# B163D.net
KiCad netlist of a schematic drawn in EAGLE
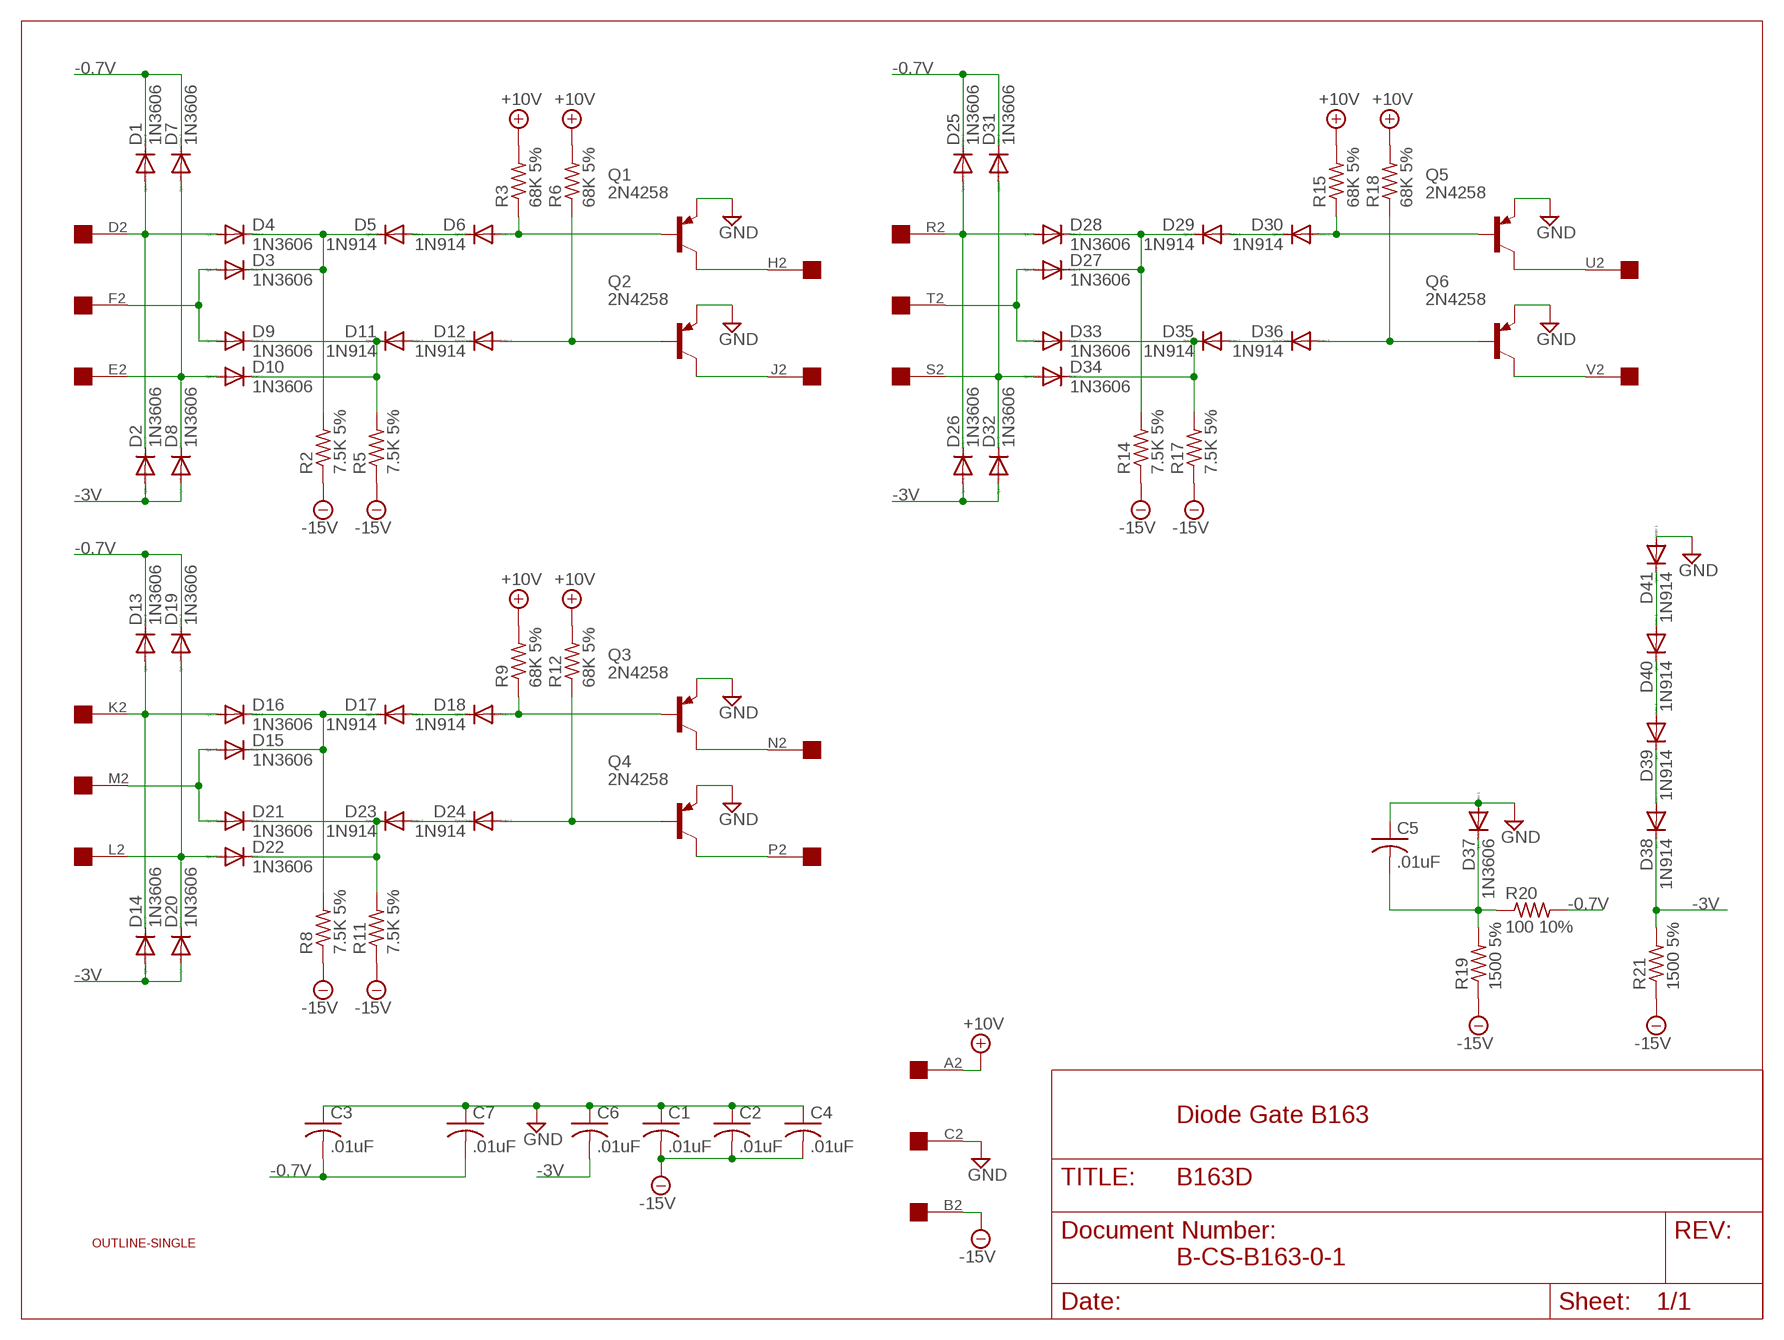
[diagram p0: schematic, sheet 1]

(export (version "E")
  (design (tool "Eeschema 10.0.6"))
  (components
    (comp (ref "C1")
      (value ".01uF")
      (footprint "eagle-import:C050-025X075")
      (libsource (lib "eagle-import") (part "C-US050-025X075"))
    )
    (comp (ref "C2")
      (value ".01uF")
      (footprint "eagle-import:C050-025X075")
      (libsource (lib "eagle-import") (part "C-US050-025X075"))
    )
    (comp (ref "C3")
      (value ".01uF")
      (footprint "eagle-import:C050-025X075")
      (libsource (lib "eagle-import") (part "C-US050-025X075"))
    )
    (comp (ref "C4")
      (value ".01uF")
      (footprint "eagle-import:C050-025X075")
      (libsource (lib "eagle-import") (part "C-US050-025X075"))
    )
    (comp (ref "C5")
      (value ".01uF")
      (footprint "eagle-import:C050-025X075")
      (libsource (lib "eagle-import") (part "C-US050-025X075"))
    )
    (comp (ref "C6")
      (value ".01uF")
      (footprint "eagle-import:C050-025X075")
      (libsource (lib "eagle-import") (part "C-US050-025X075"))
    )
    (comp (ref "C7")
      (value ".01uF")
      (footprint "eagle-import:C050-025X075")
      (libsource (lib "eagle-import") (part "C-US050-025X075"))
    )
    (comp (ref "D1")
      (value "1N3606")
      (footprint "eagle-import:DO35-10")
      (libsource (lib "eagle-import") (part "1N4148DO35-10"))
    )
    (comp (ref "D2")
      (value "1N3606")
      (footprint "eagle-import:DO35-10")
      (libsource (lib "eagle-import") (part "1N4148DO35-10"))
    )
    (comp (ref "D3")
      (value "1N3606")
      (footprint "eagle-import:DO35-10")
      (libsource (lib "eagle-import") (part "1N4148DO35-10"))
    )
    (comp (ref "D4")
      (value "1N3606")
      (footprint "eagle-import:DO35-10")
      (libsource (lib "eagle-import") (part "1N4148DO35-10"))
    )
    (comp (ref "D5")
      (value "1N914")
      (footprint "eagle-import:DO35-10")
      (libsource (lib "eagle-import") (part "1N4148DO35-10"))
    )
    (comp (ref "D6")
      (value "1N914")
      (footprint "eagle-import:DO35-10")
      (libsource (lib "eagle-import") (part "1N4148DO35-10"))
    )
    (comp (ref "D7")
      (value "1N3606")
      (footprint "eagle-import:DO35-10")
      (libsource (lib "eagle-import") (part "1N4148DO35-10"))
    )
    (comp (ref "D8")
      (value "1N3606")
      (footprint "eagle-import:DO35-10")
      (libsource (lib "eagle-import") (part "1N4148DO35-10"))
    )
    (comp (ref "D9")
      (value "1N3606")
      (footprint "eagle-import:DO35-10")
      (libsource (lib "eagle-import") (part "1N4148DO35-10"))
    )
    (comp (ref "D10")
      (value "1N3606")
      (footprint "eagle-import:DO35-10")
      (libsource (lib "eagle-import") (part "1N4148DO35-10"))
    )
    (comp (ref "D11")
      (value "1N914")
      (footprint "eagle-import:DO35-10")
      (libsource (lib "eagle-import") (part "1N4148DO35-10"))
    )
    (comp (ref "D12")
      (value "1N914")
      (footprint "eagle-import:DO35-10")
      (libsource (lib "eagle-import") (part "1N4148DO35-10"))
    )
    (comp (ref "D13")
      (value "1N3606")
      (footprint "eagle-import:DO35-10")
      (libsource (lib "eagle-import") (part "1N4148DO35-10"))
    )
    (comp (ref "D14")
      (value "1N3606")
      (footprint "eagle-import:DO35-10")
      (libsource (lib "eagle-import") (part "1N4148DO35-10"))
    )
    (comp (ref "D15")
      (value "1N3606")
      (footprint "eagle-import:DO35-10")
      (libsource (lib "eagle-import") (part "1N4148DO35-10"))
    )
    (comp (ref "D16")
      (value "1N3606")
      (footprint "eagle-import:DO35-10")
      (libsource (lib "eagle-import") (part "1N4148DO35-10"))
    )
    (comp (ref "D17")
      (value "1N914")
      (footprint "eagle-import:DO35-10")
      (libsource (lib "eagle-import") (part "1N4148DO35-10"))
    )
    (comp (ref "D18")
      (value "1N914")
      (footprint "eagle-import:DO35-10")
      (libsource (lib "eagle-import") (part "1N4148DO35-10"))
    )
    (comp (ref "D19")
      (value "1N3606")
      (footprint "eagle-import:DO35-10")
      (libsource (lib "eagle-import") (part "1N4148DO35-10"))
    )
    (comp (ref "D20")
      (value "1N3606")
      (footprint "eagle-import:DO35-10")
      (libsource (lib "eagle-import") (part "1N4148DO35-10"))
    )
    (comp (ref "D21")
      (value "1N3606")
      (footprint "eagle-import:DO35-10")
      (libsource (lib "eagle-import") (part "1N4148DO35-10"))
    )
    (comp (ref "D22")
      (value "1N3606")
      (footprint "eagle-import:DO35-10")
      (libsource (lib "eagle-import") (part "1N4148DO35-10"))
    )
    (comp (ref "D23")
      (value "1N914")
      (footprint "eagle-import:DO35-10")
      (libsource (lib "eagle-import") (part "1N4148DO35-10"))
    )
    (comp (ref "D24")
      (value "1N914")
      (footprint "eagle-import:DO35-10")
      (libsource (lib "eagle-import") (part "1N4148DO35-10"))
    )
    (comp (ref "D25")
      (value "1N3606")
      (footprint "eagle-import:DO35-10")
      (libsource (lib "eagle-import") (part "1N4148DO35-10"))
    )
    (comp (ref "D26")
      (value "1N3606")
      (footprint "eagle-import:DO35-10")
      (libsource (lib "eagle-import") (part "1N4148DO35-10"))
    )
    (comp (ref "D27")
      (value "1N3606")
      (footprint "eagle-import:DO35-10")
      (libsource (lib "eagle-import") (part "1N4148DO35-10"))
    )
    (comp (ref "D28")
      (value "1N3606")
      (footprint "eagle-import:DO35-10")
      (libsource (lib "eagle-import") (part "1N4148DO35-10"))
    )
    (comp (ref "D29")
      (value "1N914")
      (footprint "eagle-import:DO35-10")
      (libsource (lib "eagle-import") (part "1N4148DO35-10"))
    )
    (comp (ref "D30")
      (value "1N914")
      (footprint "eagle-import:DO35-10")
      (libsource (lib "eagle-import") (part "1N4148DO35-10"))
    )
    (comp (ref "D31")
      (value "1N3606")
      (footprint "eagle-import:DO35-10")
      (libsource (lib "eagle-import") (part "1N4148DO35-10"))
    )
    (comp (ref "D32")
      (value "1N3606")
      (footprint "eagle-import:DO35-10")
      (libsource (lib "eagle-import") (part "1N4148DO35-10"))
    )
    (comp (ref "D33")
      (value "1N3606")
      (footprint "eagle-import:DO35-10")
      (libsource (lib "eagle-import") (part "1N4148DO35-10"))
    )
    (comp (ref "D34")
      (value "1N3606")
      (footprint "eagle-import:DO35-10")
      (libsource (lib "eagle-import") (part "1N4148DO35-10"))
    )
    (comp (ref "D35")
      (value "1N914")
      (footprint "eagle-import:DO35-10")
      (libsource (lib "eagle-import") (part "1N4148DO35-10"))
    )
    (comp (ref "D36")
      (value "1N914")
      (footprint "eagle-import:DO35-10")
      (libsource (lib "eagle-import") (part "1N4148DO35-10"))
    )
    (comp (ref "D37")
      (value "1N3606")
      (footprint "eagle-import:DO35-10")
      (libsource (lib "eagle-import") (part "1N4148DO35-10"))
    )
    (comp (ref "D38")
      (value "1N914")
      (footprint "eagle-import:DO35-10")
      (libsource (lib "eagle-import") (part "1N4148DO35-10"))
    )
    (comp (ref "D39")
      (value "1N914")
      (footprint "eagle-import:DO35-10")
      (libsource (lib "eagle-import") (part "1N4148DO35-10"))
    )
    (comp (ref "D40")
      (value "1N914")
      (footprint "eagle-import:DO35-10")
      (libsource (lib "eagle-import") (part "1N4148DO35-10"))
    )
    (comp (ref "D41")
      (value "1N914")
      (footprint "eagle-import:DO35-10")
      (libsource (lib "eagle-import") (part "1N4148DO35-10"))
    )
    (comp (ref "Q1")
      (value "2N4258")
      (footprint "eagle-import:TO39")
      (libsource (lib "eagle-import") (part "2N2904"))
    )
    (comp (ref "Q2")
      (value "2N4258")
      (footprint "eagle-import:TO39")
      (libsource (lib "eagle-import") (part "2N2904"))
    )
    (comp (ref "Q3")
      (value "2N4258")
      (footprint "eagle-import:TO39")
      (libsource (lib "eagle-import") (part "2N2904"))
    )
    (comp (ref "Q4")
      (value "2N4258")
      (footprint "eagle-import:TO39")
      (libsource (lib "eagle-import") (part "2N2904"))
    )
    (comp (ref "Q5")
      (value "2N4258")
      (footprint "eagle-import:TO39")
      (libsource (lib "eagle-import") (part "2N2904"))
    )
    (comp (ref "Q6")
      (value "2N4258")
      (footprint "eagle-import:TO39")
      (libsource (lib "eagle-import") (part "2N2904"))
    )
    (comp (ref "R2")
      (value "7.5K 5%")
      (footprint "eagle-import:0207_10")
      (libsource (lib "eagle-import") (part "R-US_0207/10"))
    )
    (comp (ref "R3")
      (value "68K 5%")
      (footprint "eagle-import:0207_10")
      (libsource (lib "eagle-import") (part "R-US_0207/10"))
    )
    (comp (ref "R5")
      (value "7.5K 5%")
      (footprint "eagle-import:0207_10")
      (libsource (lib "eagle-import") (part "R-US_0207/10"))
    )
    (comp (ref "R6")
      (value "68K 5%")
      (footprint "eagle-import:0207_10")
      (libsource (lib "eagle-import") (part "R-US_0207/10"))
    )
    (comp (ref "R8")
      (value "7.5K 5%")
      (footprint "eagle-import:0207_10")
      (libsource (lib "eagle-import") (part "R-US_0207/10"))
    )
    (comp (ref "R9")
      (value "68K 5%")
      (footprint "eagle-import:0207_10")
      (libsource (lib "eagle-import") (part "R-US_0207/10"))
    )
    (comp (ref "R11")
      (value "7.5K 5%")
      (footprint "eagle-import:0207_10")
      (libsource (lib "eagle-import") (part "R-US_0207/10"))
    )
    (comp (ref "R12")
      (value "68K 5%")
      (footprint "eagle-import:0207_10")
      (libsource (lib "eagle-import") (part "R-US_0207/10"))
    )
    (comp (ref "R14")
      (value "7.5K 5%")
      (footprint "eagle-import:0207_10")
      (libsource (lib "eagle-import") (part "R-US_0207/10"))
    )
    (comp (ref "R15")
      (value "68K 5%")
      (footprint "eagle-import:0207_10")
      (libsource (lib "eagle-import") (part "R-US_0207/10"))
    )
    (comp (ref "R17")
      (value "7.5K 5%")
      (footprint "eagle-import:0207_10")
      (libsource (lib "eagle-import") (part "R-US_0207/10"))
    )
    (comp (ref "R18")
      (value "68K 5%")
      (footprint "eagle-import:0207_10")
      (libsource (lib "eagle-import") (part "R-US_0207/10"))
    )
    (comp (ref "R19")
      (value "1500 5%")
      (footprint "eagle-import:0207_10")
      (libsource (lib "eagle-import") (part "R-US_0207/10"))
    )
    (comp (ref "R20")
      (value "100 10%")
      (footprint "eagle-import:0207_10")
      (libsource (lib "eagle-import") (part "R-US_0207/10"))
    )
    (comp (ref "R21")
      (value "1500 5%")
      (footprint "eagle-import:0207_10")
      (libsource (lib "eagle-import") (part "R-US_0207/10"))
    )
    (comp (ref "U$1")
      (value "OUTLINE-SINGLE")
      (footprint "eagle-import:SINGLE")
      (libsource (lib "eagle-import") (part "OUTLINE-SINGLE"))
    )
    (comp (ref "U$2")
      (value "EDGE-1")
      (footprint "eagle-import:EDGE-CON1")
      (libsource (lib "eagle-import") (part "EDGE-1"))
    )
  )
  (nets
    (net (code "1") (name "+10V") (class "Default")
      (node (ref "R12") (pin "2") (pinfunction "2_2") (pintype "passive"))
      (node (ref "R15") (pin "2") (pinfunction "2_2") (pintype "passive"))
      (node (ref "R18") (pin "2") (pinfunction "2_2") (pintype "passive"))
      (node (ref "R3") (pin "2") (pinfunction "2_2") (pintype "passive"))
      (node (ref "R6") (pin "2") (pinfunction "2_2") (pintype "passive"))
      (node (ref "R9") (pin "2") (pinfunction "2_2") (pintype "passive"))
      (node (ref "U$2") (pin "A2") (pinfunction "1_A2") (pintype "bidirectional"))
    )
    (net (code "2") (name "-15V") (class "Default")
      (node (ref "C1") (pin "2") (pinfunction "2_2") (pintype "passive"))
      (node (ref "C2") (pin "2") (pinfunction "2_2") (pintype "passive"))
      (node (ref "C4") (pin "2") (pinfunction "2_2") (pintype "passive"))
      (node (ref "R11") (pin "1") (pinfunction "1_1") (pintype "passive"))
      (node (ref "R14") (pin "1") (pinfunction "1_1") (pintype "passive"))
      (node (ref "R17") (pin "1") (pinfunction "1_1") (pintype "passive"))
      (node (ref "R19") (pin "1") (pinfunction "1_1") (pintype "passive"))
      (node (ref "R2") (pin "1") (pinfunction "1_1") (pintype "passive"))
      (node (ref "R21") (pin "1") (pinfunction "1_1") (pintype "passive"))
      (node (ref "R5") (pin "1") (pinfunction "1_1") (pintype "passive"))
      (node (ref "R8") (pin "1") (pinfunction "1_1") (pintype "passive"))
      (node (ref "U$2") (pin "B2") (pinfunction "1_B2") (pintype "bidirectional"))
    )
    (net (code "3") (name "/-0.7V") (class "Default")
      (node (ref "C3") (pin "2") (pinfunction "2_2") (pintype "passive"))
      (node (ref "C7") (pin "2") (pinfunction "2_2") (pintype "passive"))
      (node (ref "D1") (pin "C") (pinfunction "C_C") (pintype "passive"))
      (node (ref "D13") (pin "C") (pinfunction "C_C") (pintype "passive"))
      (node (ref "D19") (pin "C") (pinfunction "C_C") (pintype "passive"))
      (node (ref "D25") (pin "C") (pinfunction "C_C") (pintype "passive"))
      (node (ref "D31") (pin "C") (pinfunction "C_C") (pintype "passive"))
      (node (ref "D7") (pin "C") (pinfunction "C_C") (pintype "passive"))
      (node (ref "R20") (pin "2") (pinfunction "2_2") (pintype "passive"))
    )
    (net (code "4") (name "/-3V") (class "Default")
      (node (ref "C6") (pin "2") (pinfunction "2_2") (pintype "passive"))
      (node (ref "D14") (pin "A") (pinfunction "A_A") (pintype "passive"))
      (node (ref "D2") (pin "A") (pinfunction "A_A") (pintype "passive"))
      (node (ref "D20") (pin "A") (pinfunction "A_A") (pintype "passive"))
      (node (ref "D26") (pin "A") (pinfunction "A_A") (pintype "passive"))
      (node (ref "D32") (pin "A") (pinfunction "A_A") (pintype "passive"))
      (node (ref "D38") (pin "C") (pinfunction "C_C") (pintype "passive"))
      (node (ref "D8") (pin "A") (pinfunction "A_A") (pintype "passive"))
      (node (ref "R21") (pin "2") (pinfunction "2_2") (pintype "passive"))
    )
    (net (code "5") (name "GND") (class "Default")
      (node (ref "C1") (pin "1") (pinfunction "1_1") (pintype "passive"))
      (node (ref "C2") (pin "1") (pinfunction "1_1") (pintype "passive"))
      (node (ref "C3") (pin "1") (pinfunction "1_1") (pintype "passive"))
      (node (ref "C4") (pin "1") (pinfunction "1_1") (pintype "passive"))
      (node (ref "C5") (pin "1") (pinfunction "1_1") (pintype "passive"))
      (node (ref "C6") (pin "1") (pinfunction "1_1") (pintype "passive"))
      (node (ref "C7") (pin "1") (pinfunction "1_1") (pintype "passive"))
      (node (ref "D37") (pin "A") (pinfunction "A_A") (pintype "passive"))
      (node (ref "D41") (pin "A") (pinfunction "A_A") (pintype "passive"))
      (node (ref "Q1") (pin "1") (pinfunction "E_1") (pintype "passive"))
      (node (ref "Q2") (pin "1") (pinfunction "E_1") (pintype "passive"))
      (node (ref "Q3") (pin "1") (pinfunction "E_1") (pintype "passive"))
      (node (ref "Q4") (pin "1") (pinfunction "E_1") (pintype "passive"))
      (node (ref "Q5") (pin "1") (pinfunction "E_1") (pintype "passive"))
      (node (ref "Q6") (pin "1") (pinfunction "E_1") (pintype "passive"))
      (node (ref "U$2") (pin "C2") (pinfunction "1_C2") (pintype "bidirectional"))
    )
    (net (code "6") (name "Net-(C5-Pad2)") (class "Default")
      (node (ref "C5") (pin "2") (pinfunction "2_2") (pintype "passive"))
      (node (ref "D37") (pin "C") (pinfunction "C_C") (pintype "passive"))
      (node (ref "R19") (pin "2") (pinfunction "2_2") (pintype "passive"))
      (node (ref "R20") (pin "1") (pinfunction "1_1") (pintype "passive"))
    )
    (net (code "7") (name "Net-(D3-PadC)") (class "Default")
      (node (ref "D3") (pin "C") (pinfunction "C_C") (pintype "passive"))
      (node (ref "D4") (pin "C") (pinfunction "C_C") (pintype "passive"))
      (node (ref "D5") (pin "C") (pinfunction "C_C") (pintype "passive"))
      (node (ref "R2") (pin "2") (pinfunction "2_2") (pintype "passive"))
    )
    (net (code "8") (name "Net-(D5-PadA)") (class "Default")
      (node (ref "D5") (pin "A") (pinfunction "A_A") (pintype "passive"))
      (node (ref "D6") (pin "C") (pinfunction "C_C") (pintype "passive"))
    )
    (net (code "9") (name "Net-(D10-PadC)") (class "Default")
      (node (ref "D10") (pin "C") (pinfunction "C_C") (pintype "passive"))
      (node (ref "D11") (pin "C") (pinfunction "C_C") (pintype "passive"))
      (node (ref "D9") (pin "C") (pinfunction "C_C") (pintype "passive"))
      (node (ref "R5") (pin "2") (pinfunction "2_2") (pintype "passive"))
    )
    (net (code "10") (name "Net-(D11-PadA)") (class "Default")
      (node (ref "D11") (pin "A") (pinfunction "A_A") (pintype "passive"))
      (node (ref "D12") (pin "C") (pinfunction "C_C") (pintype "passive"))
    )
    (net (code "11") (name "Net-(D15-PadC)") (class "Default")
      (node (ref "D15") (pin "C") (pinfunction "C_C") (pintype "passive"))
      (node (ref "D16") (pin "C") (pinfunction "C_C") (pintype "passive"))
      (node (ref "D17") (pin "C") (pinfunction "C_C") (pintype "passive"))
      (node (ref "R8") (pin "2") (pinfunction "2_2") (pintype "passive"))
    )
    (net (code "12") (name "Net-(D17-PadA)") (class "Default")
      (node (ref "D17") (pin "A") (pinfunction "A_A") (pintype "passive"))
      (node (ref "D18") (pin "C") (pinfunction "C_C") (pintype "passive"))
    )
    (net (code "13") (name "Net-(D21-PadC)") (class "Default")
      (node (ref "D21") (pin "C") (pinfunction "C_C") (pintype "passive"))
      (node (ref "D22") (pin "C") (pinfunction "C_C") (pintype "passive"))
      (node (ref "D23") (pin "C") (pinfunction "C_C") (pintype "passive"))
      (node (ref "R11") (pin "2") (pinfunction "2_2") (pintype "passive"))
    )
    (net (code "14") (name "Net-(D23-PadA)") (class "Default")
      (node (ref "D23") (pin "A") (pinfunction "A_A") (pintype "passive"))
      (node (ref "D24") (pin "C") (pinfunction "C_C") (pintype "passive"))
    )
    (net (code "15") (name "Net-(D27-PadC)") (class "Default")
      (node (ref "D27") (pin "C") (pinfunction "C_C") (pintype "passive"))
      (node (ref "D28") (pin "C") (pinfunction "C_C") (pintype "passive"))
      (node (ref "D29") (pin "C") (pinfunction "C_C") (pintype "passive"))
      (node (ref "R14") (pin "2") (pinfunction "2_2") (pintype "passive"))
    )
    (net (code "16") (name "Net-(D29-PadA)") (class "Default")
      (node (ref "D29") (pin "A") (pinfunction "A_A") (pintype "passive"))
      (node (ref "D30") (pin "C") (pinfunction "C_C") (pintype "passive"))
    )
    (net (code "17") (name "Net-(D33-PadC)") (class "Default")
      (node (ref "D33") (pin "C") (pinfunction "C_C") (pintype "passive"))
      (node (ref "D34") (pin "C") (pinfunction "C_C") (pintype "passive"))
      (node (ref "D35") (pin "C") (pinfunction "C_C") (pintype "passive"))
      (node (ref "R17") (pin "2") (pinfunction "2_2") (pintype "passive"))
    )
    (net (code "18") (name "Net-(D35-PadA)") (class "Default")
      (node (ref "D35") (pin "A") (pinfunction "A_A") (pintype "passive"))
      (node (ref "D36") (pin "C") (pinfunction "C_C") (pintype "passive"))
    )
    (net (code "19") (name "Net-(D38-PadA)") (class "Default")
      (node (ref "D38") (pin "A") (pinfunction "A_A") (pintype "passive"))
      (node (ref "D39") (pin "C") (pinfunction "C_C") (pintype "passive"))
    )
    (net (code "20") (name "Net-(D39-PadA)") (class "Default")
      (node (ref "D39") (pin "A") (pinfunction "A_A") (pintype "passive"))
      (node (ref "D40") (pin "C") (pinfunction "C_C") (pintype "passive"))
    )
    (net (code "21") (name "Net-(D40-PadA)") (class "Default")
      (node (ref "D40") (pin "A") (pinfunction "A_A") (pintype "passive"))
      (node (ref "D41") (pin "C") (pinfunction "C_C") (pintype "passive"))
    )
    (net (code "22") (name "Net-(Q1-B)") (class "Default")
      (node (ref "D6") (pin "A") (pinfunction "A_A") (pintype "passive"))
      (node (ref "Q1") (pin "2") (pinfunction "B_2") (pintype "passive"))
      (node (ref "R3") (pin "1") (pinfunction "1_1") (pintype "passive"))
    )
    (net (code "23") (name "Net-(Q1-C)") (class "Default")
      (node (ref "Q1") (pin "3") (pinfunction "C_3") (pintype "passive"))
      (node (ref "U$2") (pin "H2") (pinfunction "1_H2") (pintype "bidirectional"))
    )
    (net (code "24") (name "Net-(Q2-B)") (class "Default")
      (node (ref "D12") (pin "A") (pinfunction "A_A") (pintype "passive"))
      (node (ref "Q2") (pin "2") (pinfunction "B_2") (pintype "passive"))
      (node (ref "R6") (pin "1") (pinfunction "1_1") (pintype "passive"))
    )
    (net (code "25") (name "Net-(Q2-C)") (class "Default")
      (node (ref "Q2") (pin "3") (pinfunction "C_3") (pintype "passive"))
      (node (ref "U$2") (pin "J2") (pinfunction "1_J2") (pintype "bidirectional"))
    )
    (net (code "26") (name "Net-(Q3-B)") (class "Default")
      (node (ref "D18") (pin "A") (pinfunction "A_A") (pintype "passive"))
      (node (ref "Q3") (pin "2") (pinfunction "B_2") (pintype "passive"))
      (node (ref "R9") (pin "1") (pinfunction "1_1") (pintype "passive"))
    )
    (net (code "27") (name "Net-(Q3-C)") (class "Default")
      (node (ref "Q3") (pin "3") (pinfunction "C_3") (pintype "passive"))
      (node (ref "U$2") (pin "N2") (pinfunction "1_N2") (pintype "bidirectional"))
    )
    (net (code "28") (name "Net-(Q4-B)") (class "Default")
      (node (ref "D24") (pin "A") (pinfunction "A_A") (pintype "passive"))
      (node (ref "Q4") (pin "2") (pinfunction "B_2") (pintype "passive"))
      (node (ref "R12") (pin "1") (pinfunction "1_1") (pintype "passive"))
    )
    (net (code "29") (name "Net-(Q4-C)") (class "Default")
      (node (ref "Q4") (pin "3") (pinfunction "C_3") (pintype "passive"))
      (node (ref "U$2") (pin "P2") (pinfunction "1_P2") (pintype "bidirectional"))
    )
    (net (code "30") (name "Net-(Q5-B)") (class "Default")
      (node (ref "D30") (pin "A") (pinfunction "A_A") (pintype "passive"))
      (node (ref "Q5") (pin "2") (pinfunction "B_2") (pintype "passive"))
      (node (ref "R15") (pin "1") (pinfunction "1_1") (pintype "passive"))
    )
    (net (code "31") (name "Net-(Q5-C)") (class "Default")
      (node (ref "Q5") (pin "3") (pinfunction "C_3") (pintype "passive"))
      (node (ref "U$2") (pin "U2") (pinfunction "1_U2") (pintype "bidirectional"))
    )
    (net (code "32") (name "Net-(Q6-B)") (class "Default")
      (node (ref "D36") (pin "A") (pinfunction "A_A") (pintype "passive"))
      (node (ref "Q6") (pin "2") (pinfunction "B_2") (pintype "passive"))
      (node (ref "R18") (pin "1") (pinfunction "1_1") (pintype "passive"))
    )
    (net (code "33") (name "Net-(Q6-C)") (class "Default")
      (node (ref "Q6") (pin "3") (pinfunction "C_3") (pintype "passive"))
      (node (ref "U$2") (pin "V2") (pinfunction "1_V2") (pintype "bidirectional"))
    )
    (net (code "34") (name "Net-(U$2D-1)") (class "Default")
      (node (ref "D1") (pin "A") (pinfunction "A_A") (pintype "passive"))
      (node (ref "D2") (pin "C") (pinfunction "C_C") (pintype "passive"))
      (node (ref "D4") (pin "A") (pinfunction "A_A") (pintype "passive"))
      (node (ref "U$2") (pin "D2") (pinfunction "1_D2") (pintype "bidirectional"))
    )
    (net (code "35") (name "Net-(U$2E-1)") (class "Default")
      (node (ref "D10") (pin "A") (pinfunction "A_A") (pintype "passive"))
      (node (ref "D7") (pin "A") (pinfunction "A_A") (pintype "passive"))
      (node (ref "D8") (pin "C") (pinfunction "C_C") (pintype "passive"))
      (node (ref "U$2") (pin "E2") (pinfunction "1_E2") (pintype "bidirectional"))
    )
    (net (code "36") (name "Net-(U$2F-1)") (class "Default")
      (node (ref "D3") (pin "A") (pinfunction "A_A") (pintype "passive"))
      (node (ref "D9") (pin "A") (pinfunction "A_A") (pintype "passive"))
      (node (ref "U$2") (pin "F2") (pinfunction "1_F2") (pintype "bidirectional"))
    )
    (net (code "37") (name "Net-(U$2I-1)") (class "Default")
      (node (ref "D13") (pin "A") (pinfunction "A_A") (pintype "passive"))
      (node (ref "D14") (pin "C") (pinfunction "C_C") (pintype "passive"))
      (node (ref "D16") (pin "A") (pinfunction "A_A") (pintype "passive"))
      (node (ref "U$2") (pin "K2") (pinfunction "1_K2") (pintype "bidirectional"))
    )
    (net (code "38") (name "Net-(U$2J-1)") (class "Default")
      (node (ref "D19") (pin "A") (pinfunction "A_A") (pintype "passive"))
      (node (ref "D20") (pin "C") (pinfunction "C_C") (pintype "passive"))
      (node (ref "D22") (pin "A") (pinfunction "A_A") (pintype "passive"))
      (node (ref "U$2") (pin "L2") (pinfunction "1_L2") (pintype "bidirectional"))
    )
    (net (code "39") (name "Net-(U$2K-1)") (class "Default")
      (node (ref "D15") (pin "A") (pinfunction "A_A") (pintype "passive"))
      (node (ref "D21") (pin "A") (pinfunction "A_A") (pintype "passive"))
      (node (ref "U$2") (pin "M2") (pinfunction "1_M2") (pintype "bidirectional"))
    )
    (net (code "40") (name "Net-(U$2N-1)") (class "Default")
      (node (ref "D25") (pin "A") (pinfunction "A_A") (pintype "passive"))
      (node (ref "D26") (pin "C") (pinfunction "C_C") (pintype "passive"))
      (node (ref "D28") (pin "A") (pinfunction "A_A") (pintype "passive"))
      (node (ref "U$2") (pin "R2") (pinfunction "1_R2") (pintype "bidirectional"))
    )
    (net (code "41") (name "Net-(U$2O-1)") (class "Default")
      (node (ref "D31") (pin "A") (pinfunction "A_A") (pintype "passive"))
      (node (ref "D32") (pin "C") (pinfunction "C_C") (pintype "passive"))
      (node (ref "D34") (pin "A") (pinfunction "A_A") (pintype "passive"))
      (node (ref "U$2") (pin "S2") (pinfunction "1_S2") (pintype "bidirectional"))
    )
    (net (code "42") (name "Net-(U$2P-1)") (class "Default")
      (node (ref "D27") (pin "A") (pinfunction "A_A") (pintype "passive"))
      (node (ref "D33") (pin "A") (pinfunction "A_A") (pintype "passive"))
      (node (ref "U$2") (pin "T2") (pinfunction "1_T2") (pintype "bidirectional"))
    )
  )
)
